# bgt-pwr-dist.net
KiCad netlist of a schematic drawn in EAGLE
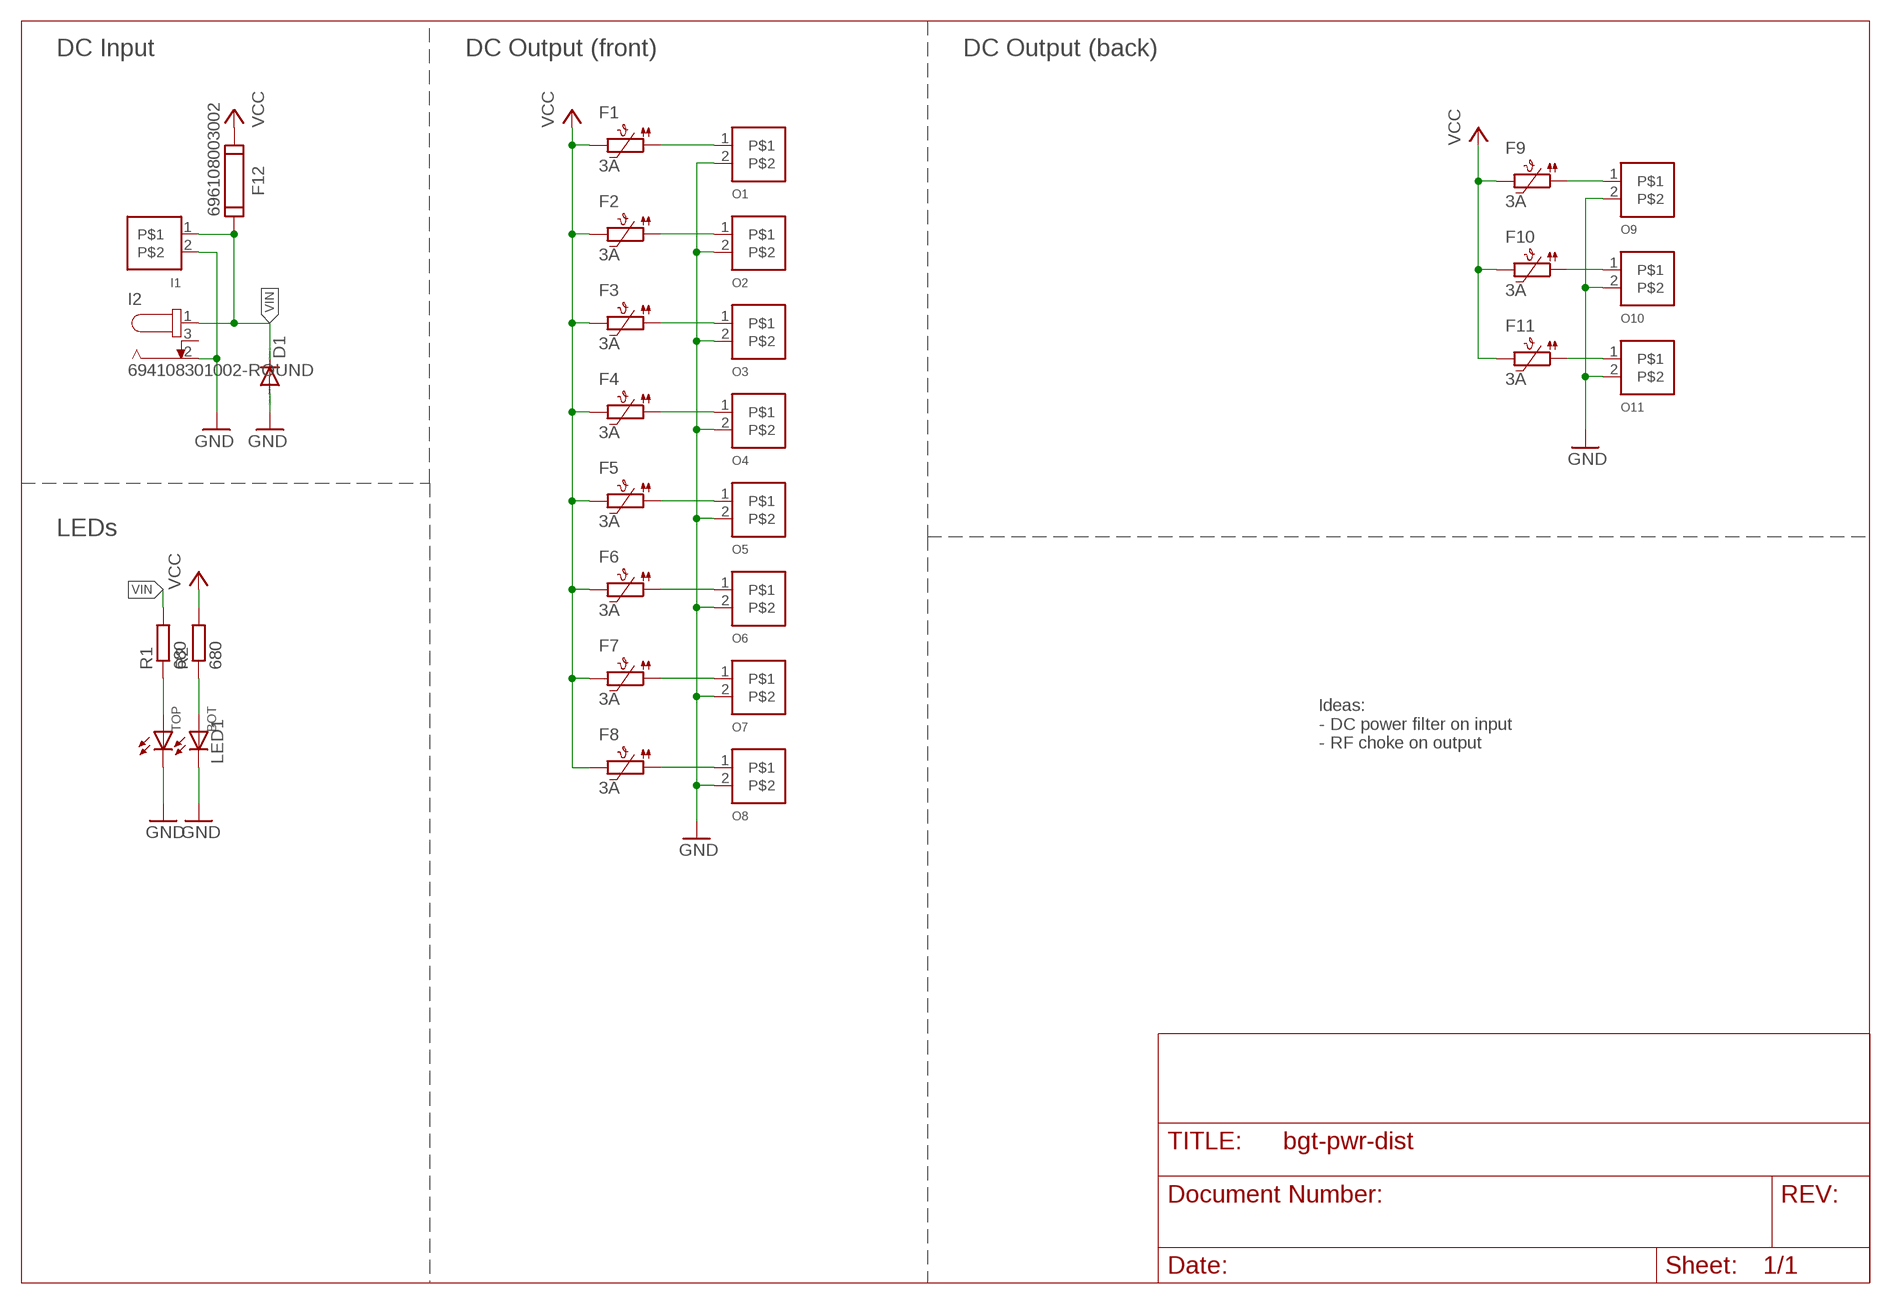
[diagram p0: schematic, sheet 1]

(export (version "E")
  (design (tool "Eeschema 10.0.6"))
  (components
    (comp (ref "D1")
      (value "DIODE-DO201-15")
      (footprint "eagle-import:DO201-15")
      (description "DIODE ZENER 14V 5W DO15")
      (fields
        (field (name "MANUFACTURER") "Micro Commercial Co")
        (field (name "MANUFACTURERPARTNUMBER") "1N5351B")
      )
      (libsource (lib "eagle-import") (part "DIODE-DO201-15"))
    )
    (comp (ref "F1")
      (value "3A")
      (footprint "eagle-import:16R300G")
      (description "PTC RESET FUSE 16V 3A RADIAL")
      (fields (field (name "MANUFACTURER") "LITTELFUSE") (field (name "MANUFACTURERPARTNUMBER") "16R300GPR"))
      (libsource (lib "eagle-import") (part "POLYFUSE16R300G"))
    )
    (comp (ref "F2")
      (value "3A")
      (footprint "eagle-import:16R300G")
      (description "PTC RESET FUSE 16V 3A RADIAL")
      (fields (field (name "MANUFACTURER") "LITTELFUSE") (field (name "MANUFACTURERPARTNUMBER") "16R300GPR"))
      (libsource (lib "eagle-import") (part "POLYFUSE16R300G"))
    )
    (comp (ref "F3")
      (value "3A")
      (footprint "eagle-import:16R300G")
      (description "PTC RESET FUSE 16V 3A RADIAL")
      (fields (field (name "MANUFACTURER") "LITTELFUSE") (field (name "MANUFACTURERPARTNUMBER") "16R300GPR"))
      (libsource (lib "eagle-import") (part "POLYFUSE16R300G"))
    )
    (comp (ref "F4")
      (value "3A")
      (footprint "eagle-import:16R300G")
      (description "PTC RESET FUSE 16V 3A RADIAL")
      (fields (field (name "MANUFACTURER") "LITTELFUSE") (field (name "MANUFACTURERPARTNUMBER") "16R300GPR"))
      (libsource (lib "eagle-import") (part "POLYFUSE16R300G"))
    )
    (comp (ref "F5")
      (value "3A")
      (footprint "eagle-import:16R300G")
      (description "PTC RESET FUSE 16V 3A RADIAL")
      (fields (field (name "MANUFACTURER") "LITTELFUSE") (field (name "MANUFACTURERPARTNUMBER") "16R300GPR"))
      (libsource (lib "eagle-import") (part "POLYFUSE16R300G"))
    )
    (comp (ref "F6")
      (value "3A")
      (footprint "eagle-import:16R300G")
      (description "PTC RESET FUSE 16V 3A RADIAL")
      (fields (field (name "MANUFACTURER") "LITTELFUSE") (field (name "MANUFACTURERPARTNUMBER") "16R300GPR"))
      (libsource (lib "eagle-import") (part "POLYFUSE16R300G"))
    )
    (comp (ref "F7")
      (value "3A")
      (footprint "eagle-import:16R300G")
      (description "PTC RESET FUSE 16V 3A RADIAL")
      (fields (field (name "MANUFACTURER") "LITTELFUSE") (field (name "MANUFACTURERPARTNUMBER") "16R300GPR"))
      (libsource (lib "eagle-import") (part "POLYFUSE16R300G"))
    )
    (comp (ref "F8")
      (value "3A")
      (footprint "eagle-import:16R300G")
      (description "PTC RESET FUSE 16V 3A RADIAL")
      (fields (field (name "MANUFACTURER") "LITTELFUSE") (field (name "MANUFACTURERPARTNUMBER") "16R300GPR"))
      (libsource (lib "eagle-import") (part "POLYFUSE16R300G"))
    )
    (comp (ref "F9")
      (value "3A")
      (footprint "eagle-import:16R300G")
      (description "PTC RESET FUSE 16V 3A RADIAL")
      (fields (field (name "MANUFACTURER") "LITTELFUSE") (field (name "MANUFACTURERPARTNUMBER") "16R300GPR"))
      (libsource (lib "eagle-import") (part "POLYFUSE16R300G"))
    )
    (comp (ref "F10")
      (value "3A")
      (footprint "eagle-import:16R300G")
      (description "PTC RESET FUSE 16V 3A RADIAL")
      (fields (field (name "MANUFACTURER") "LITTELFUSE") (field (name "MANUFACTURERPARTNUMBER") "16R300GPR"))
      (libsource (lib "eagle-import") (part "POLYFUSE16R300G"))
    )
    (comp (ref "F11")
      (value "3A")
      (footprint "eagle-import:16R300G")
      (description "PTC RESET FUSE 16V 3A RADIAL")
      (fields (field (name "MANUFACTURER") "LITTELFUSE") (field (name "MANUFACTURERPARTNUMBER") "16R300GPR"))
      (libsource (lib "eagle-import") (part "POLYFUSE16R300G"))
    )
    (comp (ref "F12")
      (value "696108003002")
      (footprint "eagle-import:696108003002")
      (description "FUSEHOLDER BLOCKS - PCB - CLIP C")
      (fields (field (name "MANUFACTURER") "Wuerth Elektronik"))
      (libsource (lib "eagle-import") (part "696108003002"))
    )
    (comp (ref "I1")
      (value "RIA_1X2-230")
      (footprint "eagle-import:RIA230")
      (description "NO DESCRIPTION")
      (fields
        (field (name "MANUFACTURER") "CUI Devices")
        (field (name "MANUFACTURERPARTNUMBER") "TBP01R1-508-02BE")
      )
      (libsource (lib "eagle-import") (part "RIA_1X2-230"))
    )
    (comp (ref "I2")
      (value "694108301002-ROUND")
      (footprint "eagle-import:694108301002_ROUND")
      (description "CONN PWR JACK 2.5X5.5MM SOLDER")
      (fields
        (field (name "MANUFACTURER") "Würth Elektronik")
        (field (name "MANUFACTURERPARTNUMBER") "694108301002")
      )
      (libsource (lib "eagle-import") (part "694108301002-ROUND"))
    )
    (comp (ref "LED1")
      (value "WP934MD")
      (footprint "eagle-import:T-1")
      (description "LED 3MM BI-LEVEL 565NM GRN DIFF")
      (fields
        (field (name "MANUFACTURER") "Kingbright")
        (field (name "MANUFACTURERPARTNUMBER") "WP934MD/2GD")
      )
      (libsource (lib "eagle-import") (part "WP934MD"))
    )
    (comp (ref "O1")
      (value "RIA_1X2-382")
      (footprint "eagle-import:RIA382-02")
      (description "NO DESCRIPTION")
      (fields
        (field (name "MANUFACTURER") "CUI DEVICES")
        (field (name "MANUFACTURERPARTNUMBER") "TBP02R1-381-02BE")
      )
      (libsource (lib "eagle-import") (part "RIA_1X2-382"))
    )
    (comp (ref "O2")
      (value "RIA_1X2-382")
      (footprint "eagle-import:RIA382-02")
      (description "NO DESCRIPTION")
      (fields
        (field (name "MANUFACTURER") "CUI DEVICES")
        (field (name "MANUFACTURERPARTNUMBER") "TBP02R1-381-02BE")
      )
      (libsource (lib "eagle-import") (part "RIA_1X2-382"))
    )
    (comp (ref "O3")
      (value "RIA_1X2-382")
      (footprint "eagle-import:RIA382-02")
      (description "NO DESCRIPTION")
      (fields
        (field (name "MANUFACTURER") "CUI DEVICES")
        (field (name "MANUFACTURERPARTNUMBER") "TBP02R1-381-02BE")
      )
      (libsource (lib "eagle-import") (part "RIA_1X2-382"))
    )
    (comp (ref "O4")
      (value "RIA_1X2-382")
      (footprint "eagle-import:RIA382-02")
      (description "NO DESCRIPTION")
      (fields
        (field (name "MANUFACTURER") "CUI DEVICES")
        (field (name "MANUFACTURERPARTNUMBER") "TBP02R1-381-02BE")
      )
      (libsource (lib "eagle-import") (part "RIA_1X2-382"))
    )
    (comp (ref "O5")
      (value "RIA_1X2-382")
      (footprint "eagle-import:RIA382-02")
      (description "NO DESCRIPTION")
      (fields
        (field (name "MANUFACTURER") "CUI DEVICES")
        (field (name "MANUFACTURERPARTNUMBER") "TBP02R1-381-02BE")
      )
      (libsource (lib "eagle-import") (part "RIA_1X2-382"))
    )
    (comp (ref "O6")
      (value "RIA_1X2-382")
      (footprint "eagle-import:RIA382-02")
      (description "NO DESCRIPTION")
      (fields
        (field (name "MANUFACTURER") "CUI DEVICES")
        (field (name "MANUFACTURERPARTNUMBER") "TBP02R1-381-02BE")
      )
      (libsource (lib "eagle-import") (part "RIA_1X2-382"))
    )
    (comp (ref "O7")
      (value "RIA_1X2-382")
      (footprint "eagle-import:RIA382-02")
      (description "NO DESCRIPTION")
      (fields
        (field (name "MANUFACTURER") "CUI DEVICES")
        (field (name "MANUFACTURERPARTNUMBER") "TBP02R1-381-02BE")
      )
      (libsource (lib "eagle-import") (part "RIA_1X2-382"))
    )
    (comp (ref "O8")
      (value "RIA_1X2-382")
      (footprint "eagle-import:RIA382-02")
      (description "NO DESCRIPTION")
      (fields
        (field (name "MANUFACTURER") "CUI DEVICES")
        (field (name "MANUFACTURERPARTNUMBER") "TBP02R1-381-02BE")
      )
      (libsource (lib "eagle-import") (part "RIA_1X2-382"))
    )
    (comp (ref "O9")
      (value "RIA_1X2-382")
      (footprint "eagle-import:RIA382-02")
      (description "NO DESCRIPTION")
      (fields
        (field (name "MANUFACTURER") "CUI DEVICES")
        (field (name "MANUFACTURERPARTNUMBER") "TBP02R1-381-02BE")
      )
      (libsource (lib "eagle-import") (part "RIA_1X2-382"))
    )
    (comp (ref "O10")
      (value "RIA_1X2-382")
      (footprint "eagle-import:RIA382-02")
      (description "NO DESCRIPTION")
      (fields
        (field (name "MANUFACTURER") "CUI DEVICES")
        (field (name "MANUFACTURERPARTNUMBER") "TBP02R1-381-02BE")
      )
      (libsource (lib "eagle-import") (part "RIA_1X2-382"))
    )
    (comp (ref "O11")
      (value "RIA_1X2-382")
      (footprint "eagle-import:RIA382-02")
      (description "NO DESCRIPTION")
      (fields
        (field (name "MANUFACTURER") "CUI DEVICES")
        (field (name "MANUFACTURERPARTNUMBER") "TBP02R1-381-02BE")
      )
      (libsource (lib "eagle-import") (part "RIA_1X2-382"))
    )
    (comp (ref "R1")
      (value "680")
      (footprint "eagle-import:0207_10")
      (description "RES 680 OHM 5% 1/4W AXIAL")
      (fields
        (field (name "MANUFACTURER") "UNKNOWN MANUFACTURER")
        (field (name "MANUFACTURERPARTNUMBER") "CF14JT680R")
      )
      (libsource (lib "eagle-import") (part "R-EU_0207/10"))
    )
    (comp (ref "R2")
      (value "680")
      (footprint "eagle-import:0207_10")
      (description "RES 680 OHM 5% 1/4W AXIAL")
      (fields
        (field (name "MANUFACTURER") "UNKNOWN MANUFACTURER")
        (field (name "MANUFACTURERPARTNUMBER") "CF14JT680R")
      )
      (libsource (lib "eagle-import") (part "R-EU_0207/10"))
    )
  )
  (nets
    (net (code "1") (name "GND") (class "Default")
      (node (ref "D1") (pin "A") (pinfunction "A_A") (pintype "passive"))
      (node (ref "I1") (pin "2") (pinfunction "P$2_2") (pintype "bidirectional"))
      (node (ref "I2") (pin "2") (pinfunction "2_2") (pintype "passive"))
      (node (ref "LED1") (pin "1") (pinfunction "CT_1") (pintype "passive"))
      (node (ref "LED1") (pin "3") (pinfunction "CB_3") (pintype "passive"))
      (node (ref "O1") (pin "2") (pinfunction "P$2_2") (pintype "bidirectional"))
      (node (ref "O10") (pin "2") (pinfunction "P$2_2") (pintype "bidirectional"))
      (node (ref "O11") (pin "2") (pinfunction "P$2_2") (pintype "bidirectional"))
      (node (ref "O2") (pin "2") (pinfunction "P$2_2") (pintype "bidirectional"))
      (node (ref "O3") (pin "2") (pinfunction "P$2_2") (pintype "bidirectional"))
      (node (ref "O4") (pin "2") (pinfunction "P$2_2") (pintype "bidirectional"))
      (node (ref "O5") (pin "2") (pinfunction "P$2_2") (pintype "bidirectional"))
      (node (ref "O6") (pin "2") (pinfunction "P$2_2") (pintype "bidirectional"))
      (node (ref "O7") (pin "2") (pinfunction "P$2_2") (pintype "bidirectional"))
      (node (ref "O8") (pin "2") (pinfunction "P$2_2") (pintype "bidirectional"))
      (node (ref "O9") (pin "2") (pinfunction "P$2_2") (pintype "bidirectional"))
    )
    (net (code "2") (name "Net-(LED1-AB)") (class "Default")
      (node (ref "LED1") (pin "4") (pinfunction "AB_4") (pintype "passive"))
      (node (ref "R2") (pin "1") (pinfunction "1_1") (pintype "passive"))
    )
    (net (code "3") (name "Net-(LED1-AT)") (class "Default")
      (node (ref "LED1") (pin "2") (pinfunction "AT_2") (pintype "passive"))
      (node (ref "R1") (pin "1") (pinfunction "1_1") (pintype "passive"))
    )
    (net (code "4") (name "Net-(O1-P$1)") (class "Default")
      (node (ref "F1") (pin "1") (pinfunction "1_1") (pintype "passive"))
      (node (ref "O1") (pin "1") (pinfunction "P$1_1") (pintype "bidirectional"))
    )
    (net (code "5") (name "Net-(O2-P$1)") (class "Default")
      (node (ref "F2") (pin "1") (pinfunction "1_1") (pintype "passive"))
      (node (ref "O2") (pin "1") (pinfunction "P$1_1") (pintype "bidirectional"))
    )
    (net (code "6") (name "Net-(O3-P$1)") (class "Default")
      (node (ref "F3") (pin "1") (pinfunction "1_1") (pintype "passive"))
      (node (ref "O3") (pin "1") (pinfunction "P$1_1") (pintype "bidirectional"))
    )
    (net (code "7") (name "Net-(O4-P$1)") (class "Default")
      (node (ref "F4") (pin "1") (pinfunction "1_1") (pintype "passive"))
      (node (ref "O4") (pin "1") (pinfunction "P$1_1") (pintype "bidirectional"))
    )
    (net (code "8") (name "Net-(O5-P$1)") (class "Default")
      (node (ref "F5") (pin "1") (pinfunction "1_1") (pintype "passive"))
      (node (ref "O5") (pin "1") (pinfunction "P$1_1") (pintype "bidirectional"))
    )
    (net (code "9") (name "Net-(O6-P$1)") (class "Default")
      (node (ref "F6") (pin "1") (pinfunction "1_1") (pintype "passive"))
      (node (ref "O6") (pin "1") (pinfunction "P$1_1") (pintype "bidirectional"))
    )
    (net (code "10") (name "Net-(O7-P$1)") (class "Default")
      (node (ref "F7") (pin "1") (pinfunction "1_1") (pintype "passive"))
      (node (ref "O7") (pin "1") (pinfunction "P$1_1") (pintype "bidirectional"))
    )
    (net (code "11") (name "Net-(O8-P$1)") (class "Default")
      (node (ref "F8") (pin "1") (pinfunction "1_1") (pintype "passive"))
      (node (ref "O8") (pin "1") (pinfunction "P$1_1") (pintype "bidirectional"))
    )
    (net (code "12") (name "Net-(O9-P$1)") (class "Default")
      (node (ref "F9") (pin "1") (pinfunction "1_1") (pintype "passive"))
      (node (ref "O9") (pin "1") (pinfunction "P$1_1") (pintype "bidirectional"))
    )
    (net (code "13") (name "Net-(O10-P$1)") (class "Default")
      (node (ref "F10") (pin "1") (pinfunction "1_1") (pintype "passive"))
      (node (ref "O10") (pin "1") (pinfunction "P$1_1") (pintype "bidirectional"))
    )
    (net (code "14") (name "Net-(O11-P$1)") (class "Default")
      (node (ref "F11") (pin "1") (pinfunction "1_1") (pintype "passive"))
      (node (ref "O11") (pin "1") (pinfunction "P$1_1") (pintype "bidirectional"))
    )
    (net (code "15") (name "VCC") (class "Default")
      (node (ref "F1") (pin "2") (pinfunction "2_2") (pintype "passive"))
      (node (ref "F10") (pin "2") (pinfunction "2_2") (pintype "passive"))
      (node (ref "F11") (pin "2") (pinfunction "2_2") (pintype "passive"))
      (node (ref "F12") (pin "2") (pinfunction "2_2") (pintype "passive"))
      (node (ref "F2") (pin "2") (pinfunction "2_2") (pintype "passive"))
      (node (ref "F3") (pin "2") (pinfunction "2_2") (pintype "passive"))
      (node (ref "F4") (pin "2") (pinfunction "2_2") (pintype "passive"))
      (node (ref "F5") (pin "2") (pinfunction "2_2") (pintype "passive"))
      (node (ref "F6") (pin "2") (pinfunction "2_2") (pintype "passive"))
      (node (ref "F7") (pin "2") (pinfunction "2_2") (pintype "passive"))
      (node (ref "F8") (pin "2") (pinfunction "2_2") (pintype "passive"))
      (node (ref "F9") (pin "2") (pinfunction "2_2") (pintype "passive"))
      (node (ref "R2") (pin "2") (pinfunction "2_2") (pintype "passive"))
    )
    (net (code "16") (name "VIN") (class "Default")
      (node (ref "D1") (pin "C") (pinfunction "C_C") (pintype "passive"))
      (node (ref "F12") (pin "1") (pinfunction "1_1") (pintype "passive"))
      (node (ref "I1") (pin "1") (pinfunction "P$1_1") (pintype "bidirectional"))
      (node (ref "I2") (pin "1") (pinfunction "1_1") (pintype "passive"))
      (node (ref "R1") (pin "2") (pinfunction "2_2") (pintype "passive"))
    )
    (net (code "17") (name "unconnected-(I2-Pad3)") (class "Default")
      (node (ref "I2") (pin "3") (pinfunction "3_3") (pintype "passive"))
    )
  )
)
